# schematic.net
KiCad netlist of a schematic drawn in EAGLE
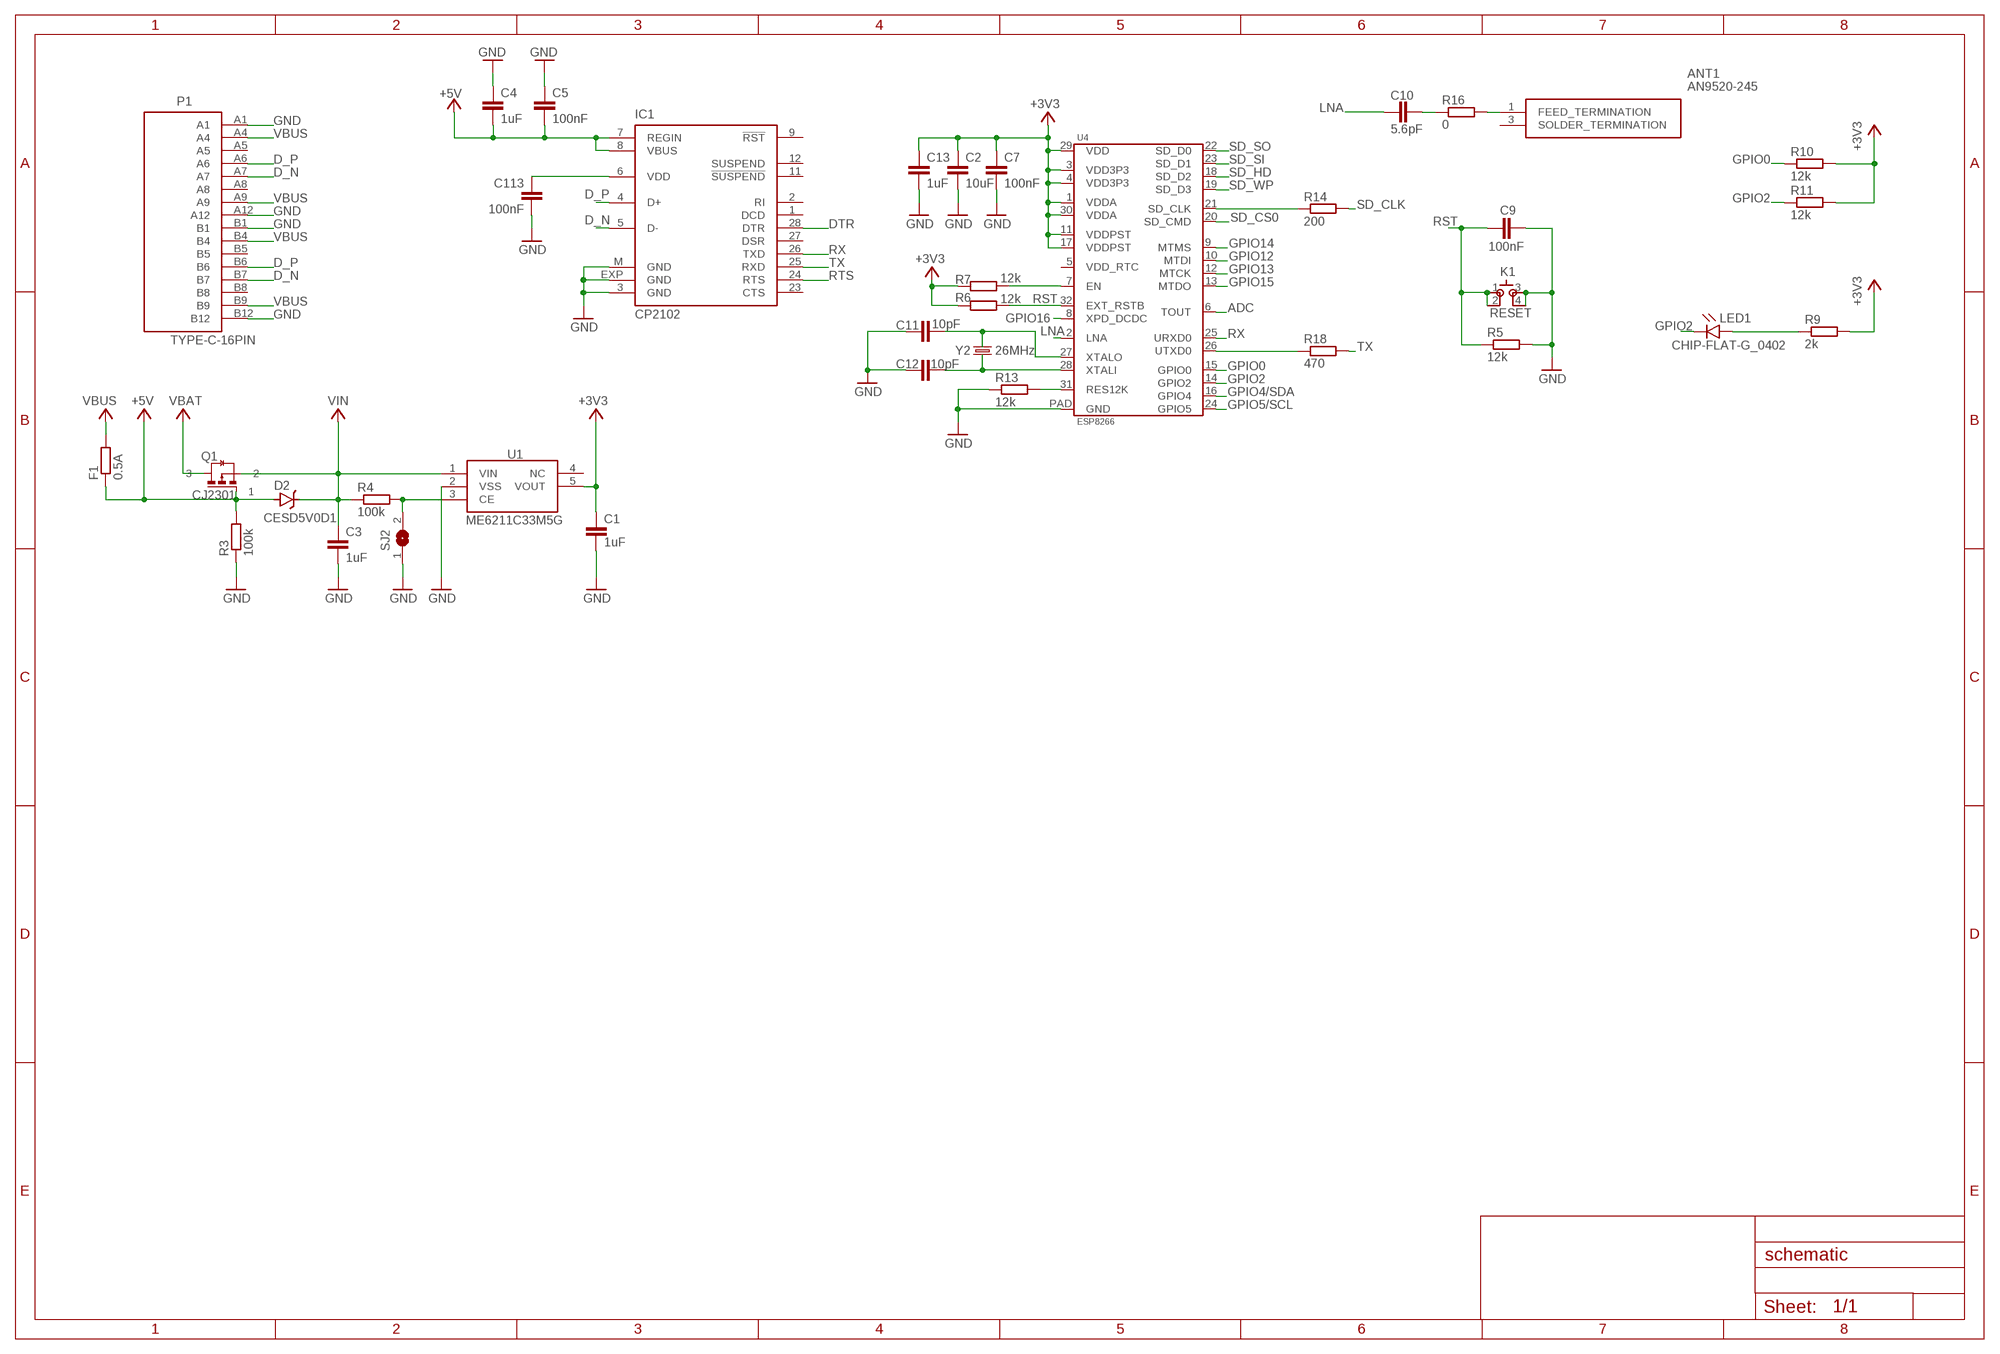
[diagram p0: schematic, sheet 1]

(export (version "E")
  (design (tool "Eeschema 10.0.6"))
  (components
    (comp (ref "ANT1")
      (value "AN9520-245")
      (footprint "eagle-import:AN9520245")
      (libsource (lib "eagle-import") (part "AN9520-245"))
    )
    (comp (ref "C1")
      (value "1uF")
      (footprint "eagle-import:C0402")
      (libsource (lib "eagle-import") (part "C-EUC0402"))
    )
    (comp (ref "C2")
      (value "10uF")
      (footprint "eagle-import:C0402")
      (libsource (lib "eagle-import") (part "C-EUC0402"))
    )
    (comp (ref "C3")
      (value "1uF")
      (footprint "eagle-import:C0402")
      (libsource (lib "eagle-import") (part "C-EUC0402"))
    )
    (comp (ref "C4")
      (value "1uF")
      (footprint "eagle-import:C0402")
      (libsource (lib "eagle-import") (part "C-EUC0402"))
    )
    (comp (ref "C5")
      (value "100nF")
      (footprint "eagle-import:C0402")
      (libsource (lib "eagle-import") (part "C-EUC0402"))
    )
    (comp (ref "C7")
      (value "100nF")
      (footprint "eagle-import:C0402")
      (libsource (lib "eagle-import") (part "C-EUC0402"))
    )
    (comp (ref "C9")
      (value "100nF")
      (footprint "eagle-import:C0402")
      (libsource (lib "eagle-import") (part "C-EUC0402"))
    )
    (comp (ref "C10")
      (value "5.6pF")
      (footprint "eagle-import:C0402")
      (libsource (lib "eagle-import") (part "C-EUC0402"))
    )
    (comp (ref "C11")
      (value "10pF")
      (footprint "eagle-import:C0402")
      (libsource (lib "eagle-import") (part "C-EUC0402"))
    )
    (comp (ref "C12")
      (value "10pF")
      (footprint "eagle-import:C0402")
      (libsource (lib "eagle-import") (part "C-EUC0402"))
    )
    (comp (ref "C13")
      (value "1uF")
      (footprint "eagle-import:C0402")
      (libsource (lib "eagle-import") (part "C-EUC0402"))
    )
    (comp (ref "C113")
      (value "100nF")
      (footprint "eagle-import:C0402")
      (libsource (lib "eagle-import") (part "C-EUC0402"))
    )
    (comp (ref "D2")
      (value "CESD5V0D1")
      (footprint "eagle-import:SOD-123")
      (fields (field (name "MANUFACTURER") "JCET") (field (name "CREATED_BY") "PCBLayout.com"))
      (libsource (lib "eagle-import") (part "CESD5V0D1"))
    )
    (comp (ref "F1")
      (value "0.5A")
      (footprint "eagle-import:R0402")
      (libsource (lib "eagle-import") (part "R-EU_R0402"))
    )
    (comp (ref "IC1")
      (value "CP2102")
      (footprint "eagle-import:MLP28")
      (fields (field (name "MF") "FARNELL") (field (name "MPN") "CP2102-GM"))
      (libsource (lib "eagle-import") (part "CP2102"))
    )
    (comp (ref "K1")
      (value "RESET")
      (footprint "eagle-import:SKSCLDE010")
      (libsource (lib "eagle-import") (part "SKSCLDE010"))
    )
    (comp (ref "LED1")
      (value "CHIP-FLAT-G_0402")
      (footprint "eagle-import:LEDC1005X25N_FLAT-G")
      (libsource (lib "eagle-import") (part "CHIP-FLAT-G_0402"))
    )
    (comp (ref "P1")
      (value "TYPE-C-16PIN")
      (footprint "eagle-import:TYPE-C-16PIN")
      (libsource (lib "eagle-import") (part "TYPE-C-16PIN"))
    )
    (comp (ref "Q1")
      (value "CJ2301")
      (footprint "eagle-import:SOT95P240X115-3N")
      (libsource (lib "eagle-import") (part "CJ2301"))
    )
    (comp (ref "R3")
      (value "100k")
      (footprint "eagle-import:R0402")
      (libsource (lib "eagle-import") (part "R-EU_R0402"))
    )
    (comp (ref "R4")
      (value "100k")
      (footprint "eagle-import:R0402")
      (libsource (lib "eagle-import") (part "R-EU_R0402"))
    )
    (comp (ref "R5")
      (value "12k")
      (footprint "eagle-import:R0402")
      (libsource (lib "eagle-import") (part "R-EU_R0402"))
    )
    (comp (ref "R6")
      (value "12k")
      (footprint "eagle-import:R0402")
      (libsource (lib "eagle-import") (part "R-EU_R0402"))
    )
    (comp (ref "R7")
      (value "12k")
      (footprint "eagle-import:R0402")
      (libsource (lib "eagle-import") (part "R-EU_R0402"))
    )
    (comp (ref "R9")
      (value "2k")
      (footprint "eagle-import:R0402")
      (libsource (lib "eagle-import") (part "R-EU_R0402"))
    )
    (comp (ref "R10")
      (value "12k")
      (footprint "eagle-import:R0402")
      (libsource (lib "eagle-import") (part "R-EU_R0402"))
    )
    (comp (ref "R11")
      (value "12k")
      (footprint "eagle-import:R0402")
      (libsource (lib "eagle-import") (part "R-EU_R0402"))
    )
    (comp (ref "R13")
      (value "12k")
      (footprint "eagle-import:R0402")
      (libsource (lib "eagle-import") (part "R-EU_R0402"))
    )
    (comp (ref "R14")
      (value "200")
      (footprint "eagle-import:R0402")
      (libsource (lib "eagle-import") (part "R-EU_R0402"))
    )
    (comp (ref "R16")
      (value "0")
      (footprint "eagle-import:R0603")
      (libsource (lib "eagle-import") (part "R-EU_R0603"))
    )
    (comp (ref "R18")
      (value "470")
      (footprint "eagle-import:R0402")
      (libsource (lib "eagle-import") (part "R-EU_R0402"))
    )
    (comp (ref "SJ2") (value "SJ") (footprint "eagle-import:SJ") (libsource (lib "eagle-import") (part "SJ")))
    (comp (ref "U1")
      (value "ME6211C33M5G")
      (footprint "eagle-import:SOT95P282X145-5N")
      (libsource (lib "eagle-import") (part "ME6211C33M5G"))
    )
    (comp (ref "U4")
      (value "ESP8266")
      (footprint "eagle-import:ESP8266")
      (libsource (lib "eagle-import") (part "ESP8266"))
    )
    (comp (ref "Y2")
      (value "26MHz")
      (footprint "eagle-import:SMD-3225-4")
      (fields (field (name "SPICEPREFIX") "B"))
      (libsource (lib "eagle-import") (part "YSX321SL"))
    )
  )
  (nets
    (net (code "1") (name "+3V3") (class "Default")
      (node (ref "C1") (pin "1") (pinfunction "1_1") (pintype "passive"))
      (node (ref "C13") (pin "1") (pinfunction "1_1") (pintype "passive"))
      (node (ref "C2") (pin "1") (pinfunction "1_1") (pintype "passive"))
      (node (ref "C7") (pin "1") (pinfunction "1_1") (pintype "passive"))
      (node (ref "R10") (pin "2") (pinfunction "2_2") (pintype "passive"))
      (node (ref "R11") (pin "2") (pinfunction "2_2") (pintype "passive"))
      (node (ref "R6") (pin "1") (pinfunction "1_1") (pintype "passive"))
      (node (ref "R7") (pin "1") (pinfunction "1_1") (pintype "passive"))
      (node (ref "R9") (pin "2") (pinfunction "2_2") (pintype "passive"))
      (node (ref "U1") (pin "5") (pinfunction "VOUT_5") (pintype "bidirectional"))
      (node (ref "U4") (pin "1") (pinfunction "VDDA_1") (pintype "bidirectional"))
      (node (ref "U4") (pin "11") (pinfunction "VDDPST_11") (pintype "bidirectional"))
      (node (ref "U4") (pin "17") (pinfunction "VDDPST_17") (pintype "bidirectional"))
      (node (ref "U4") (pin "29") (pinfunction "VDD_29") (pintype "bidirectional"))
      (node (ref "U4") (pin "3") (pinfunction "VDD3P3_3") (pintype "bidirectional"))
      (node (ref "U4") (pin "30") (pinfunction "VDDA_30") (pintype "bidirectional"))
      (node (ref "U4") (pin "4") (pinfunction "VDD3P3_4") (pintype "bidirectional"))
    )
    (net (code "2") (name "+5V") (class "Default")
      (node (ref "C4") (pin "2") (pinfunction "2_2") (pintype "passive"))
      (node (ref "C5") (pin "2") (pinfunction "2_2") (pintype "passive"))
      (node (ref "D2") (pin "A") (pinfunction "A_A") (pintype "passive"))
      (node (ref "F1") (pin "1") (pinfunction "1_1") (pintype "passive"))
      (node (ref "IC1") (pin "7") (pinfunction "REGIN_7") (pintype "passive"))
      (node (ref "IC1") (pin "8") (pinfunction "VBUS_8") (pintype "input"))
      (node (ref "Q1") (pin "1") (pinfunction "1_1") (pintype "bidirectional"))
      (node (ref "R3") (pin "2") (pinfunction "2_2") (pintype "passive"))
    )
    (net (code "3") (name "/ADC") (class "Default")
      (node (ref "U4") (pin "6") (pinfunction "TOUT_6") (pintype "bidirectional"))
    )
    (net (code "4") (name "/DTR") (class "Default")
      (node (ref "IC1") (pin "28") (pinfunction "DTR_28") (pintype "output"))
    )
    (net (code "5") (name "/D_N") (class "Default")
      (node (ref "IC1") (pin "5") (pinfunction "D-_5") (pintype "bidirectional"))
      (node (ref "P1") (pin "A7") (pinfunction "A7_A7") (pintype "bidirectional"))
      (node (ref "P1") (pin "B7") (pinfunction "B7_B7") (pintype "bidirectional"))
    )
    (net (code "6") (name "/D_P") (class "Default")
      (node (ref "IC1") (pin "4") (pinfunction "D+_4") (pintype "bidirectional"))
      (node (ref "P1") (pin "A6") (pinfunction "A6_A6") (pintype "bidirectional"))
      (node (ref "P1") (pin "B6") (pinfunction "B6_B6") (pintype "bidirectional"))
    )
    (net (code "7") (name "/GPIO0") (class "Default")
      (node (ref "R10") (pin "1") (pinfunction "1_1") (pintype "passive"))
      (node (ref "U4") (pin "15") (pinfunction "GPIO0_15") (pintype "bidirectional"))
    )
    (net (code "8") (name "/GPIO2") (class "Default")
      (node (ref "LED1") (pin "C") (pinfunction "C_C") (pintype "passive"))
      (node (ref "R11") (pin "1") (pinfunction "1_1") (pintype "passive"))
      (node (ref "U4") (pin "14") (pinfunction "GPIO2_14") (pintype "bidirectional"))
    )
    (net (code "9") (name "/GPIO4{slash}SDA") (class "Default")
      (node (ref "U4") (pin "16") (pinfunction "GPIO4_16") (pintype "bidirectional"))
    )
    (net (code "10") (name "/GPIO5{slash}SCL") (class "Default")
      (node (ref "U4") (pin "24") (pinfunction "GPIO5_24") (pintype "bidirectional"))
    )
    (net (code "11") (name "/GPIO12") (class "Default")
      (node (ref "U4") (pin "10") (pinfunction "MTDI_10") (pintype "bidirectional"))
    )
    (net (code "12") (name "/GPIO13") (class "Default")
      (node (ref "U4") (pin "12") (pinfunction "MTCK_12") (pintype "bidirectional"))
    )
    (net (code "13") (name "/GPIO14") (class "Default")
      (node (ref "U4") (pin "9") (pinfunction "MTMS_9") (pintype "bidirectional"))
    )
    (net (code "14") (name "/GPIO15") (class "Default")
      (node (ref "U4") (pin "13") (pinfunction "MTDO_13") (pintype "bidirectional"))
    )
    (net (code "15") (name "/GPIO16") (class "Default")
      (node (ref "U4") (pin "8") (pinfunction "XPD_DCDC_8") (pintype "bidirectional"))
    )
    (net (code "16") (name "/LNA") (class "Default")
      (node (ref "C10") (pin "1") (pinfunction "1_1") (pintype "passive"))
      (node (ref "U4") (pin "2") (pinfunction "LNA_2") (pintype "bidirectional"))
    )
    (net (code "17") (name "/RST") (class "Default")
      (node (ref "C9") (pin "1") (pinfunction "1_1") (pintype "passive"))
      (node (ref "K1") (pin "1") (pinfunction "1_1") (pintype "bidirectional"))
      (node (ref "K1") (pin "2") (pinfunction "2_2") (pintype "bidirectional"))
      (node (ref "R5") (pin "1") (pinfunction "1_1") (pintype "passive"))
      (node (ref "R6") (pin "2") (pinfunction "2_2") (pintype "passive"))
      (node (ref "U4") (pin "32") (pinfunction "EXT_RSTB_32") (pintype "bidirectional"))
    )
    (net (code "18") (name "/RTS") (class "Default")
      (node (ref "IC1") (pin "24") (pinfunction "RTS_24") (pintype "output"))
    )
    (net (code "19") (name "/RX") (class "Default")
      (node (ref "IC1") (pin "26") (pinfunction "TXD_26") (pintype "output"))
      (node (ref "U4") (pin "25") (pinfunction "URXD0_25") (pintype "bidirectional"))
    )
    (net (code "20") (name "/SD_CLK") (class "Default")
      (node (ref "R14") (pin "2") (pinfunction "2_2") (pintype "passive"))
    )
    (net (code "21") (name "/SD_CS0") (class "Default")
      (node (ref "U4") (pin "20") (pinfunction "SD_CMD_20") (pintype "bidirectional"))
    )
    (net (code "22") (name "/SD_HD") (class "Default")
      (node (ref "U4") (pin "18") (pinfunction "SD_D2_18") (pintype "bidirectional"))
    )
    (net (code "23") (name "/SD_SI") (class "Default")
      (node (ref "U4") (pin "23") (pinfunction "SD_D1_23") (pintype "bidirectional"))
    )
    (net (code "24") (name "/SD_SO") (class "Default")
      (node (ref "U4") (pin "22") (pinfunction "SD_D0_22") (pintype "bidirectional"))
    )
    (net (code "25") (name "/SD_WP") (class "Default")
      (node (ref "U4") (pin "19") (pinfunction "SD_D3_19") (pintype "bidirectional"))
    )
    (net (code "26") (name "/TX") (class "Default")
      (node (ref "IC1") (pin "25") (pinfunction "RXD_25") (pintype "input"))
      (node (ref "R18") (pin "2") (pinfunction "2_2") (pintype "passive"))
    )
    (net (code "27") (name "GND") (class "Default")
      (node (ref "C1") (pin "2") (pinfunction "2_2") (pintype "passive"))
      (node (ref "C11") (pin "1") (pinfunction "1_1") (pintype "passive"))
      (node (ref "C113") (pin "2") (pinfunction "2_2") (pintype "passive"))
      (node (ref "C12") (pin "1") (pinfunction "1_1") (pintype "passive"))
      (node (ref "C13") (pin "2") (pinfunction "2_2") (pintype "passive"))
      (node (ref "C2") (pin "2") (pinfunction "2_2") (pintype "passive"))
      (node (ref "C3") (pin "2") (pinfunction "2_2") (pintype "passive"))
      (node (ref "C4") (pin "1") (pinfunction "1_1") (pintype "passive"))
      (node (ref "C5") (pin "1") (pinfunction "1_1") (pintype "passive"))
      (node (ref "C7") (pin "2") (pinfunction "2_2") (pintype "passive"))
      (node (ref "C9") (pin "2") (pinfunction "2_2") (pintype "passive"))
      (node (ref "IC1") (pin "3") (pinfunction "GND_3") (pintype "power_in"))
      (node (ref "IC1") (pin "EXP") (pinfunction "GND_EXP") (pintype "power_in"))
      (node (ref "IC1") (pin "M") (pinfunction "GND_M") (pintype "power_in"))
      (node (ref "K1") (pin "3") (pinfunction "4_3") (pintype "bidirectional"))
      (node (ref "K1") (pin "4") (pinfunction "3_4") (pintype "bidirectional"))
      (node (ref "P1") (pin "A1") (pinfunction "A1_A1") (pintype "bidirectional"))
      (node (ref "P1") (pin "A12") (pinfunction "A12_A12") (pintype "bidirectional"))
      (node (ref "P1") (pin "B1") (pinfunction "B1_B1") (pintype "bidirectional"))
      (node (ref "P1") (pin "B12") (pinfunction "B12_B12") (pintype "bidirectional"))
      (node (ref "R13") (pin "1") (pinfunction "1_1") (pintype "passive"))
      (node (ref "R3") (pin "1") (pinfunction "1_1") (pintype "passive"))
      (node (ref "R5") (pin "2") (pinfunction "2_2") (pintype "passive"))
      (node (ref "SJ2") (pin "1") (pinfunction "1_1") (pintype "passive"))
      (node (ref "U1") (pin "2") (pinfunction "VSS_2") (pintype "bidirectional"))
      (node (ref "U4") (pin "PAD") (pinfunction "GND_PAD") (pintype "bidirectional"))
    )
    (net (code "28") (name "Net-(ANT1-FEED_TERMINATION)") (class "Default")
      (node (ref "ANT1") (pin "1") (pinfunction "FEED_TERMINATION_1") (pintype "bidirectional"))
      (node (ref "R16") (pin "2") (pinfunction "2_2") (pintype "passive"))
    )
    (net (code "29") (name "Net-(C10-Pad2)") (class "Default")
      (node (ref "C10") (pin "2") (pinfunction "2_2") (pintype "passive"))
      (node (ref "R16") (pin "1") (pinfunction "1_1") (pintype "passive"))
    )
    (net (code "30") (name "Net-(IC1-VDD)") (class "Default")
      (node (ref "C113") (pin "1") (pinfunction "1_1") (pintype "passive"))
      (node (ref "IC1") (pin "6") (pinfunction "VDD_6") (pintype "power_in"))
    )
    (net (code "31") (name "Net-(LED1-PadA)") (class "Default")
      (node (ref "LED1") (pin "A") (pinfunction "A_A") (pintype "passive"))
      (node (ref "R9") (pin "1") (pinfunction "1_1") (pintype "passive"))
    )
    (net (code "32") (name "Net-(U1-CE)") (class "Default")
      (node (ref "R4") (pin "2") (pinfunction "2_2") (pintype "passive"))
      (node (ref "SJ2") (pin "2") (pinfunction "2_2") (pintype "passive"))
      (node (ref "U1") (pin "3") (pinfunction "CE_3") (pintype "bidirectional"))
    )
    (net (code "33") (name "Net-(U4-EN)") (class "Default")
      (node (ref "R7") (pin "2") (pinfunction "2_2") (pintype "passive"))
      (node (ref "U4") (pin "7") (pinfunction "EN_7") (pintype "bidirectional"))
    )
    (net (code "34") (name "Net-(U4-RES12K)") (class "Default")
      (node (ref "R13") (pin "2") (pinfunction "2_2") (pintype "passive"))
      (node (ref "U4") (pin "31") (pinfunction "RES12K_31") (pintype "bidirectional"))
    )
    (net (code "35") (name "Net-(U4-SD_CLK)") (class "Default")
      (node (ref "R14") (pin "1") (pinfunction "1_1") (pintype "passive"))
      (node (ref "U4") (pin "21") (pinfunction "SD_CLK_21") (pintype "bidirectional"))
    )
    (net (code "36") (name "Net-(U4-UTXD0)") (class "Default")
      (node (ref "R18") (pin "1") (pinfunction "1_1") (pintype "passive"))
      (node (ref "U4") (pin "26") (pinfunction "UTXD0_26") (pintype "bidirectional"))
    )
    (net (code "37") (name "Net-(U4-XTALI)") (class "Default")
      (node (ref "C12") (pin "2") (pinfunction "2_2") (pintype "passive"))
      (node (ref "U4") (pin "28") (pinfunction "XTALI_28") (pintype "bidirectional"))
      (node (ref "Y2") (pin "3") (pinfunction "P$2_3") (pintype "bidirectional"))
    )
    (net (code "38") (name "Net-(U4-XTALO)") (class "Default")
      (node (ref "C11") (pin "2") (pinfunction "2_2") (pintype "passive"))
      (node (ref "U4") (pin "27") (pinfunction "XTALO_27") (pintype "bidirectional"))
      (node (ref "Y2") (pin "1") (pinfunction "P$1_1") (pintype "bidirectional"))
    )
    (net (code "39") (name "VBAT") (class "Default")
      (node (ref "Q1") (pin "3") (pinfunction "3_3") (pintype "bidirectional"))
    )
    (net (code "40") (name "VBUS") (class "Default")
      (node (ref "F1") (pin "2") (pinfunction "2_2") (pintype "passive"))
      (node (ref "P1") (pin "A4") (pinfunction "A4_A4") (pintype "bidirectional"))
      (node (ref "P1") (pin "A9") (pinfunction "A9_A9") (pintype "bidirectional"))
      (node (ref "P1") (pin "B4") (pinfunction "B4_B4") (pintype "bidirectional"))
      (node (ref "P1") (pin "B9") (pinfunction "B9_B9") (pintype "bidirectional"))
    )
    (net (code "41") (name "VIN") (class "Default")
      (node (ref "C3") (pin "1") (pinfunction "1_1") (pintype "passive"))
      (node (ref "D2") (pin "C") (pinfunction "C_C") (pintype "passive"))
      (node (ref "Q1") (pin "2") (pinfunction "2_2") (pintype "bidirectional"))
      (node (ref "R4") (pin "1") (pinfunction "1_1") (pintype "passive"))
      (node (ref "U1") (pin "1") (pinfunction "VIN_1") (pintype "bidirectional"))
    )
    (net (code "42") (name "unconnected-(ANT1-SOLDER_TERMINATION-Pad3)") (class "Default")
      (node (ref "ANT1") (pin "3") (pinfunction "SOLDER_TERMINATION_3") (pintype "bidirectional"))
    )
    (net (code "43") (name "unconnected-(IC1-CTS-Pad23)") (class "Default")
      (node (ref "IC1") (pin "23") (pinfunction "CTS_23") (pintype "input"))
    )
    (net (code "44") (name "unconnected-(IC1-DCD-Pad1)") (class "Default")
      (node (ref "IC1") (pin "1") (pinfunction "DCD_1") (pintype "input"))
    )
    (net (code "45") (name "unconnected-(IC1-DSR-Pad27)") (class "Default")
      (node (ref "IC1") (pin "27") (pinfunction "DSR_27") (pintype "input"))
    )
    (net (code "46") (name "unconnected-(IC1-RI-Pad2)") (class "Default")
      (node (ref "IC1") (pin "2") (pinfunction "RI_2") (pintype "input"))
    )
    (net (code "47") (name "unconnected-(IC1-SUSPEND-Pad12)") (class "Default")
      (node (ref "IC1") (pin "12") (pinfunction "SUSPEND_12") (pintype "output"))
    )
    (net (code "48") (name "unconnected-(IC1-~{RST}-Pad9)") (class "Default")
      (node (ref "IC1") (pin "9") (pinfunction "~{RST}_9") (pintype "bidirectional"))
    )
    (net (code "49") (name "unconnected-(IC1-~{SUSPEND}-Pad11)") (class "Default")
      (node (ref "IC1") (pin "11") (pinfunction "~{SUSPEND}_11") (pintype "output"))
    )
    (net (code "50") (name "unconnected-(P1-PadA5)") (class "Default")
      (node (ref "P1") (pin "A5") (pinfunction "A5_A5") (pintype "bidirectional"))
    )
    (net (code "51") (name "unconnected-(P1-PadA8)") (class "Default")
      (node (ref "P1") (pin "A8") (pinfunction "A8_A8") (pintype "bidirectional"))
    )
    (net (code "52") (name "unconnected-(P1-PadB5)") (class "Default")
      (node (ref "P1") (pin "B5") (pinfunction "B5_B5") (pintype "bidirectional"))
    )
    (net (code "53") (name "unconnected-(P1-PadB8)") (class "Default")
      (node (ref "P1") (pin "B8") (pinfunction "B8_B8") (pintype "bidirectional"))
    )
    (net (code "54") (name "unconnected-(U1-NC-Pad4)") (class "Default")
      (node (ref "U1") (pin "4") (pinfunction "NC_4") (pintype "no_connect"))
    )
    (net (code "55") (name "unconnected-(U4-VDD_RTC-Pad5)") (class "Default")
      (node (ref "U4") (pin "5") (pinfunction "VDD_RTC_5") (pintype "bidirectional"))
    )
  )
)
